# Narrow_AAA_sensor_v1.net
KiCad netlist of a schematic drawn in EAGLE
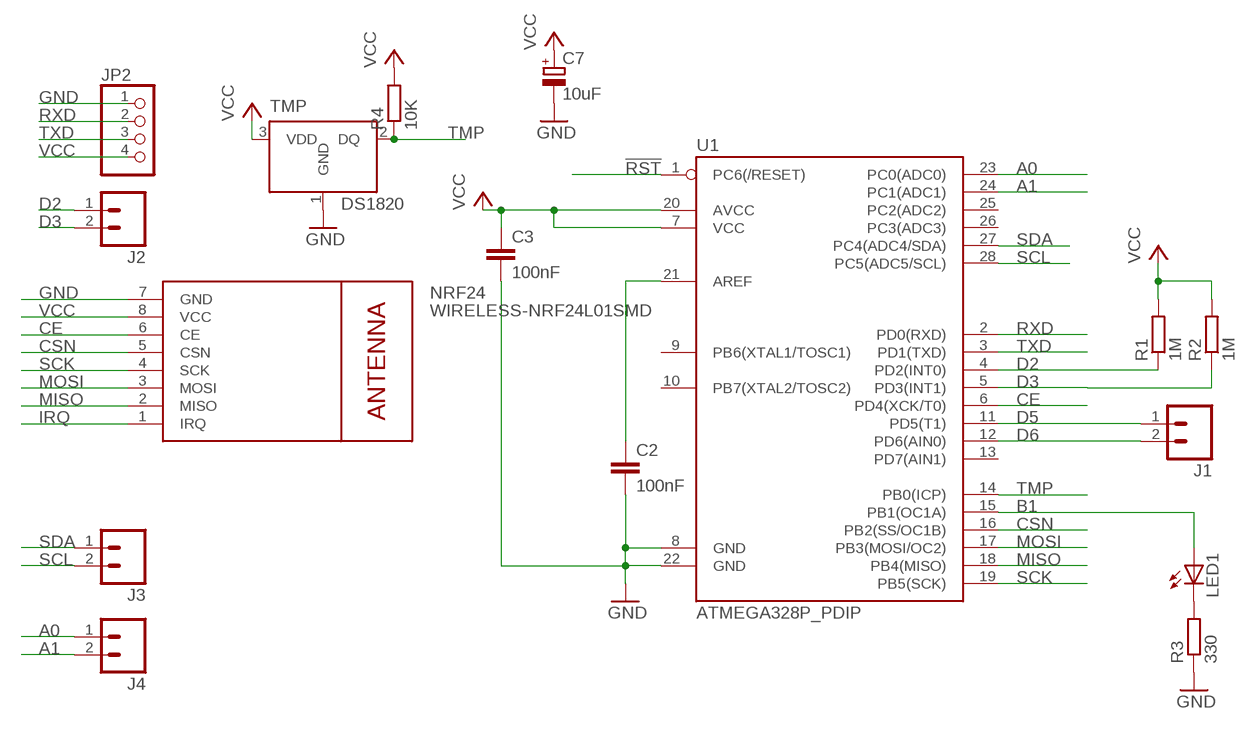
[diagram p0: schematic, sheet 1]

(export (version "E")
  (design (tool "Eeschema 10.0.6"))
  (components
    (comp (ref "C2")
      (value "100nF")
      (footprint "eagle-import:C025-025X050")
      (libsource (lib "eagle-import") (part "C-EU025-025X050"))
    )
    (comp (ref "C3")
      (value "100nF")
      (footprint "eagle-import:C025-025X050")
      (libsource (lib "eagle-import") (part "C-EU025-025X050"))
    )
    (comp (ref "C7")
      (value "10uF")
      (footprint "eagle-import:E2,5-5")
      (libsource (lib "eagle-import") (part "CPOL-EUE2.5-5"))
    )
    (comp (ref "J1")
      (value "M02PTH")
      (footprint "eagle-import:1X02")
      (libsource (lib "eagle-import") (part "M02PTH"))
    )
    (comp (ref "J2")
      (value "M02PTH")
      (footprint "eagle-import:1X02")
      (libsource (lib "eagle-import") (part "M02PTH"))
    )
    (comp (ref "J3")
      (value "M021X02_NO_SILK")
      (footprint "eagle-import:1X02_NO_SILK")
      (libsource (lib "eagle-import") (part "M021X02_NO_SILK"))
    )
    (comp (ref "J4")
      (value "M021X02_NO_SILK")
      (footprint "eagle-import:1X02_NO_SILK")
      (libsource (lib "eagle-import") (part "M021X02_NO_SILK"))
    )
    (comp (ref "JP2")
      (value "PINHD-1X4")
      (footprint "eagle-import:1X04")
      (libsource (lib "eagle-import") (part "PINHD-1X4"))
    )
    (comp (ref "LED1")
      (value "LED3MM")
      (footprint "eagle-import:LED3MM")
      (libsource (lib "eagle-import") (part "LED3MM"))
    )
    (comp (ref "NRF24")
      (value "WIRELESS-NRF24L01SMD")
      (footprint "eagle-import:WIRELESS-NRF24L01-SMD")
      (libsource (lib "eagle-import") (part "WIRELESS-NRF24L01SMD"))
    )
    (comp (ref "R1")
      (value "1M")
      (footprint "eagle-import:0204_7")
      (libsource (lib "eagle-import") (part "R-EU_0204/7"))
    )
    (comp (ref "R2")
      (value "1M")
      (footprint "eagle-import:0204_7")
      (libsource (lib "eagle-import") (part "R-EU_0204/7"))
    )
    (comp (ref "R3")
      (value "330")
      (footprint "eagle-import:0204_7")
      (libsource (lib "eagle-import") (part "R-EU_0204/7"))
    )
    (comp (ref "R4")
      (value "10K")
      (footprint "eagle-import:0204_7")
      (libsource (lib "eagle-import") (part "R-EU_0204/7"))
    )
    (comp (ref "TMP")
      (value "DS1820")
      (footprint "eagle-import:TO-92")
      (libsource (lib "eagle-import") (part "DS1820"))
    )
    (comp (ref "U1")
      (value "ATMEGA328P_PDIP")
      (footprint "eagle-import:DIL28-3")
      (libsource (lib "eagle-import") (part "ATMEGA328P_PDIP"))
    )
  )
  (nets
    (net (code "1") (name "/A0") (class "Default")
      (node (ref "J4") (pin "1") (pinfunction "1_1") (pintype "passive"))
      (node (ref "U1") (pin "23") (pinfunction "PC0(ADC0)_23") (pintype "bidirectional"))
    )
    (net (code "2") (name "/A1") (class "Default")
      (node (ref "J4") (pin "2") (pinfunction "2_2") (pintype "passive"))
      (node (ref "U1") (pin "24") (pinfunction "PC1(ADC1)_24") (pintype "bidirectional"))
    )
    (net (code "3") (name "/B1") (class "Default")
      (node (ref "LED1") (pin "A") (pinfunction "A_A") (pintype "passive"))
      (node (ref "U1") (pin "15") (pinfunction "PB1(OC1A)_15") (pintype "bidirectional"))
    )
    (net (code "4") (name "/CE") (class "Default")
      (node (ref "NRF24") (pin "6") (pinfunction "CE_6") (pintype "bidirectional"))
      (node (ref "U1") (pin "6") (pinfunction "PD4(XCK/T0)_6") (pintype "bidirectional"))
    )
    (net (code "5") (name "/CSN") (class "Default")
      (node (ref "NRF24") (pin "5") (pinfunction "CSN_5") (pintype "bidirectional"))
      (node (ref "U1") (pin "16") (pinfunction "PB2(SS/OC1B)_16") (pintype "bidirectional"))
    )
    (net (code "6") (name "/D2") (class "Default")
      (node (ref "J2") (pin "1") (pinfunction "1_1") (pintype "passive"))
      (node (ref "R1") (pin "1") (pinfunction "1_1") (pintype "passive"))
      (node (ref "U1") (pin "4") (pinfunction "PD2(INT0)_4") (pintype "bidirectional"))
    )
    (net (code "7") (name "/D3") (class "Default")
      (node (ref "J2") (pin "2") (pinfunction "2_2") (pintype "passive"))
      (node (ref "R2") (pin "1") (pinfunction "1_1") (pintype "passive"))
      (node (ref "U1") (pin "5") (pinfunction "PD3(INT1)_5") (pintype "bidirectional"))
    )
    (net (code "8") (name "/D5") (class "Default")
      (node (ref "J1") (pin "1") (pinfunction "1_1") (pintype "passive"))
      (node (ref "U1") (pin "11") (pinfunction "PD5(T1)_11") (pintype "bidirectional"))
    )
    (net (code "9") (name "/D6") (class "Default")
      (node (ref "J1") (pin "2") (pinfunction "2_2") (pintype "passive"))
      (node (ref "U1") (pin "12") (pinfunction "PD6(AIN0)_12") (pintype "bidirectional"))
    )
    (net (code "10") (name "/IRQ") (class "Default")
      (node (ref "NRF24") (pin "1") (pinfunction "IRQ_1") (pintype "bidirectional"))
    )
    (net (code "11") (name "/MISO") (class "Default")
      (node (ref "NRF24") (pin "2") (pinfunction "MISO_2") (pintype "bidirectional"))
      (node (ref "U1") (pin "18") (pinfunction "PB4(MISO)_18") (pintype "bidirectional"))
    )
    (net (code "12") (name "/MOSI") (class "Default")
      (node (ref "NRF24") (pin "3") (pinfunction "MOSI_3") (pintype "bidirectional"))
      (node (ref "U1") (pin "17") (pinfunction "PB3(MOSI/OC2)_17") (pintype "bidirectional"))
    )
    (net (code "13") (name "/RXD") (class "Default")
      (node (ref "JP2") (pin "2") (pinfunction "2_2") (pintype "passive"))
      (node (ref "U1") (pin "2") (pinfunction "PD0(RXD)_2") (pintype "bidirectional"))
    )
    (net (code "14") (name "/SCK") (class "Default")
      (node (ref "NRF24") (pin "4") (pinfunction "SCK_4") (pintype "bidirectional"))
      (node (ref "U1") (pin "19") (pinfunction "PB5(SCK)_19") (pintype "bidirectional"))
    )
    (net (code "15") (name "/SCL") (class "Default")
      (node (ref "J3") (pin "2") (pinfunction "2_2") (pintype "passive"))
      (node (ref "U1") (pin "28") (pinfunction "PC5(ADC5/SCL)_28") (pintype "bidirectional"))
    )
    (net (code "16") (name "/SDA") (class "Default")
      (node (ref "J3") (pin "1") (pinfunction "1_1") (pintype "passive"))
      (node (ref "U1") (pin "27") (pinfunction "PC4(ADC4/SDA)_27") (pintype "bidirectional"))
    )
    (net (code "17") (name "/TMP") (class "Default")
      (node (ref "R4") (pin "1") (pinfunction "1_1") (pintype "passive"))
      (node (ref "TMP") (pin "2") (pinfunction "DQ_2") (pintype "output"))
      (node (ref "U1") (pin "14") (pinfunction "PB0(ICP)_14") (pintype "bidirectional"))
    )
    (net (code "18") (name "/TXD") (class "Default")
      (node (ref "JP2") (pin "3") (pinfunction "3_3") (pintype "passive"))
      (node (ref "U1") (pin "3") (pinfunction "PD1(TXD)_3") (pintype "bidirectional"))
    )
    (net (code "19") (name "/~{RST}") (class "Default")
      (node (ref "U1") (pin "1") (pinfunction "PC6(/RESET)_1") (pintype "bidirectional"))
    )
    (net (code "20") (name "GND") (class "Default")
      (node (ref "C2") (pin "2") (pinfunction "2_2") (pintype "passive"))
      (node (ref "C3") (pin "2") (pinfunction "2_2") (pintype "passive"))
      (node (ref "C7") (pin "-") (pinfunction "-_-") (pintype "passive"))
      (node (ref "JP2") (pin "1") (pinfunction "1_1") (pintype "passive"))
      (node (ref "NRF24") (pin "7") (pinfunction "GND_7") (pintype "power_in"))
      (node (ref "R3") (pin "1") (pinfunction "1_1") (pintype "passive"))
      (node (ref "TMP") (pin "1") (pinfunction "GND_1") (pintype "power_in"))
      (node (ref "U1") (pin "22") (pinfunction "GND_22") (pintype "bidirectional"))
      (node (ref "U1") (pin "8") (pinfunction "GND_8") (pintype "bidirectional"))
    )
    (net (code "21") (name "Net-(LED1-C)") (class "Default")
      (node (ref "LED1") (pin "K") (pinfunction "C_K") (pintype "passive"))
      (node (ref "R3") (pin "2") (pinfunction "2_2") (pintype "passive"))
    )
    (net (code "22") (name "Net-(U1-AREF)") (class "Default")
      (node (ref "C2") (pin "1") (pinfunction "1_1") (pintype "passive"))
      (node (ref "U1") (pin "21") (pinfunction "AREF_21") (pintype "bidirectional"))
    )
    (net (code "23") (name "VCC") (class "Default")
      (node (ref "C3") (pin "1") (pinfunction "1_1") (pintype "passive"))
      (node (ref "C7") (pin "+") (pinfunction "+_+") (pintype "passive"))
      (node (ref "JP2") (pin "4") (pinfunction "4_4") (pintype "passive"))
      (node (ref "NRF24") (pin "8") (pinfunction "VCC_8") (pintype "power_in"))
      (node (ref "R1") (pin "2") (pinfunction "2_2") (pintype "passive"))
      (node (ref "R2") (pin "2") (pinfunction "2_2") (pintype "passive"))
      (node (ref "R4") (pin "2") (pinfunction "2_2") (pintype "passive"))
      (node (ref "TMP") (pin "3") (pinfunction "VDD_3") (pintype "input"))
      (node (ref "U1") (pin "20") (pinfunction "AVCC_20") (pintype "bidirectional"))
      (node (ref "U1") (pin "7") (pinfunction "VCC_7") (pintype "bidirectional"))
    )
    (net (code "24") (name "unconnected-(U1-PB6(XTAL1{slash}TOSC1)-Pad9)") (class "Default")
      (node (ref "U1") (pin "9") (pinfunction "PB6(XTAL1/TOSC1)_9") (pintype "bidirectional"))
    )
    (net (code "25") (name "unconnected-(U1-PB7(XTAL2{slash}TOSC2)-Pad10)") (class "Default")
      (node (ref "U1") (pin "10") (pinfunction "PB7(XTAL2/TOSC2)_10") (pintype "bidirectional"))
    )
    (net (code "26") (name "unconnected-(U1-PC2(ADC2)-Pad25)") (class "Default")
      (node (ref "U1") (pin "25") (pinfunction "PC2(ADC2)_25") (pintype "bidirectional"))
    )
    (net (code "27") (name "unconnected-(U1-PC3(ADC3)-Pad26)") (class "Default")
      (node (ref "U1") (pin "26") (pinfunction "PC3(ADC3)_26") (pintype "bidirectional"))
    )
    (net (code "28") (name "unconnected-(U1-PD7(AIN1)-Pad13)") (class "Default")
      (node (ref "U1") (pin "13") (pinfunction "PD7(AIN1)_13") (pintype "bidirectional"))
    )
  )
)
